# Power_cape.net
KiCad netlist of a schematic drawn in EAGLE
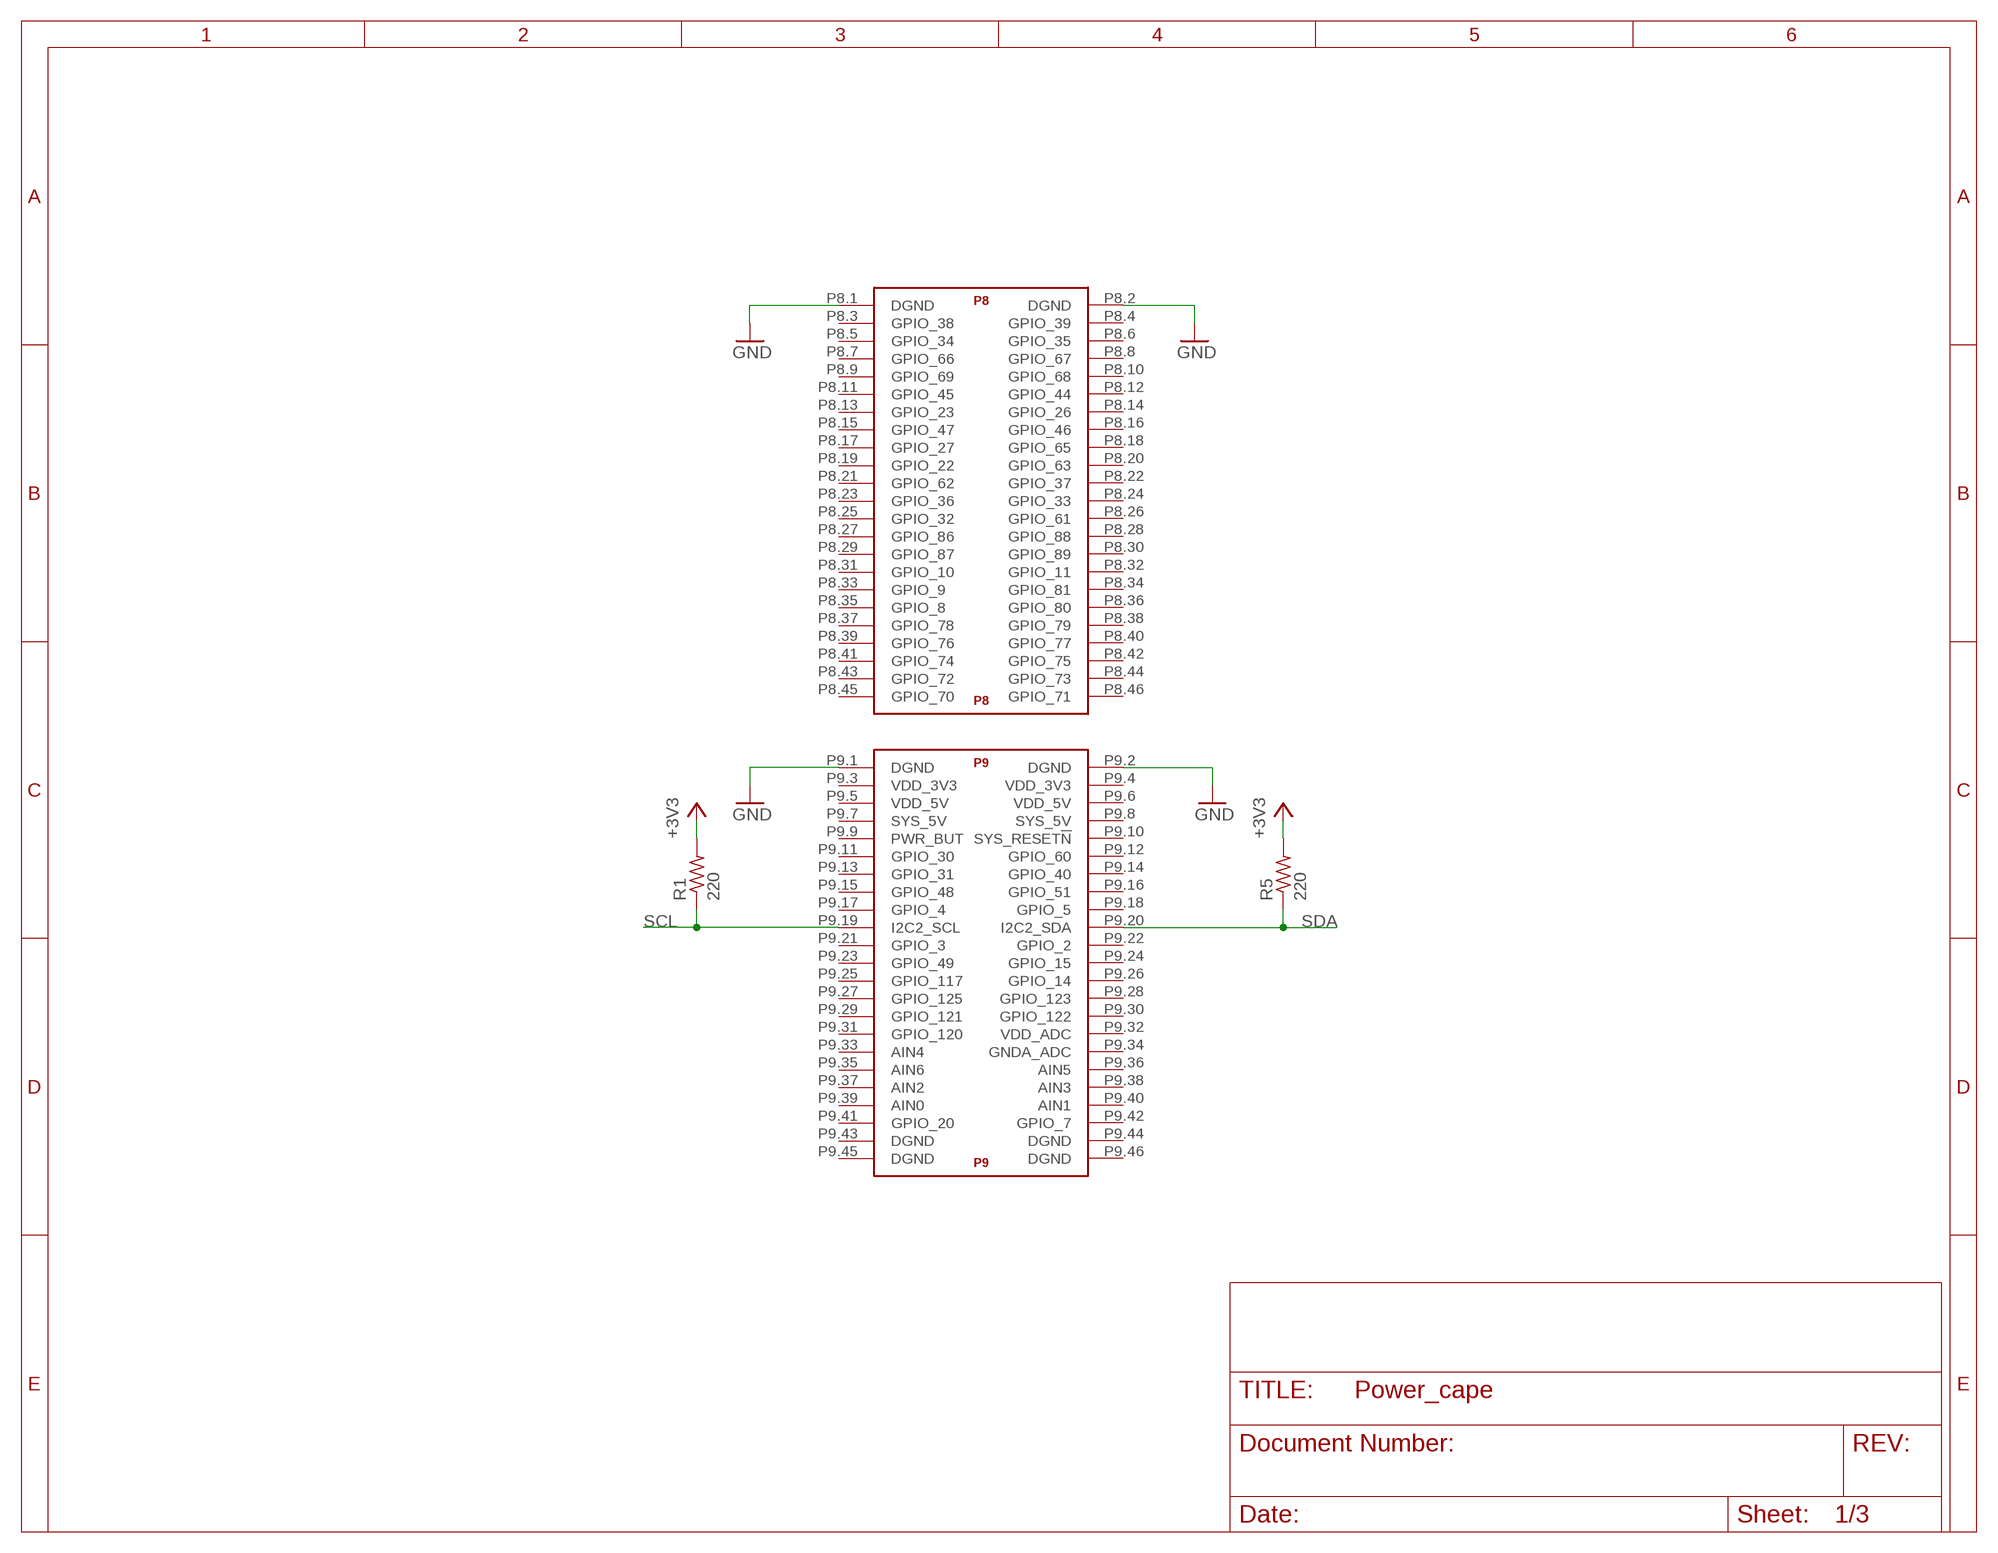
[diagram p0: schematic, sheet 1]
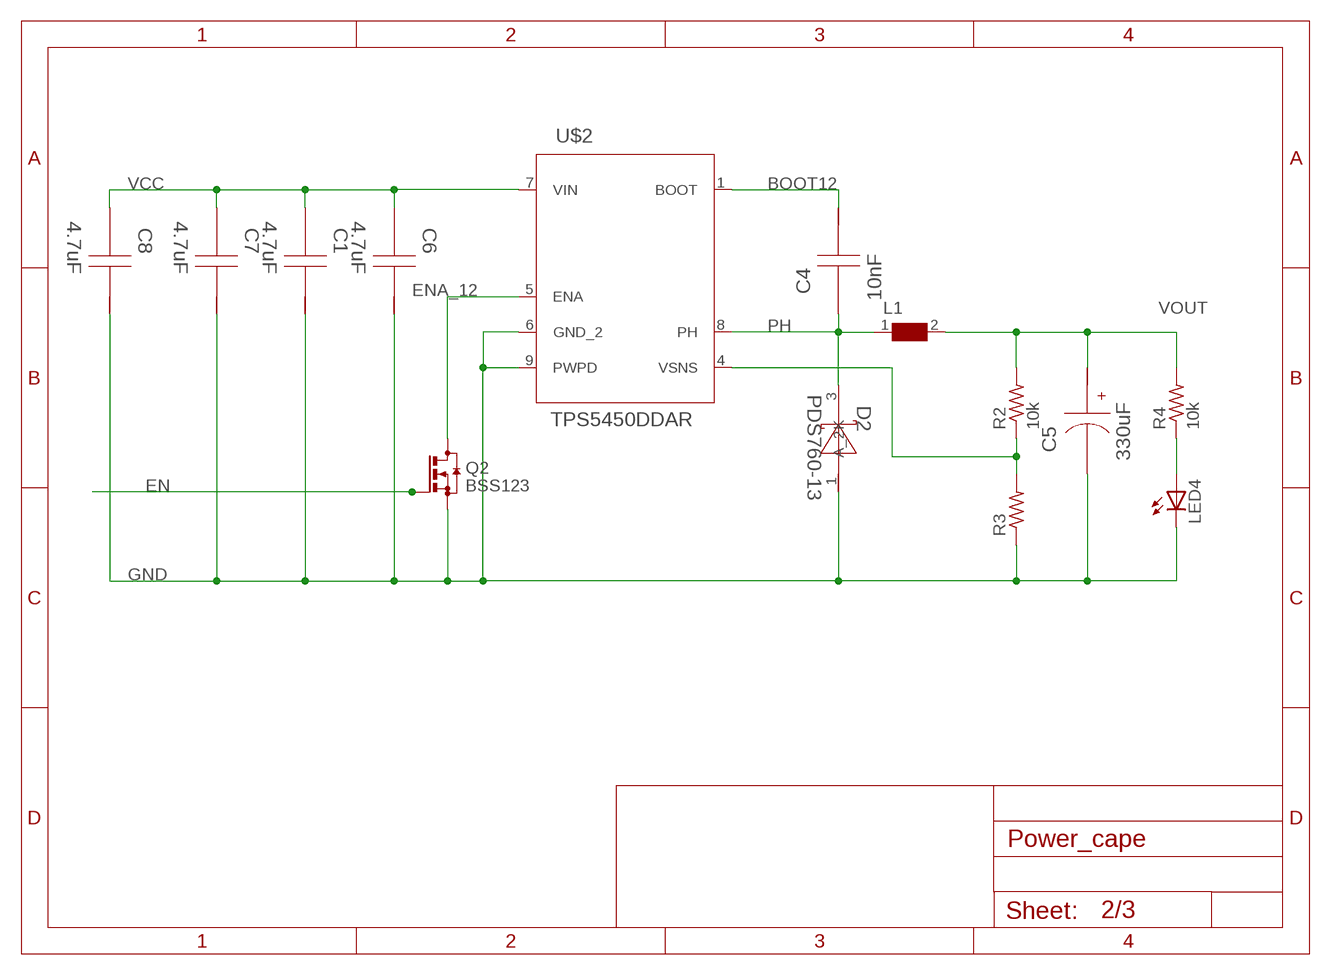
[diagram p1: schematic, sheet 2]

(export (version "E")
  (design (tool "Eeschema 10.0.6"))
  (components
    (comp (ref "C1")
      (value "4.7uF")
      (footprint "eagle-import:1206")
      (fields (field (name "MANUFACTURER_PART_NUMBER") "GRM31CR71H475KA12L"))
      (libsource (lib "eagle-import") (part "GRM31CR71H475KA12L"))
    )
    (comp (ref "C4")
      (value "10nF")
      (footprint "eagle-import:0805")
      (fields (field (name "MANUFACTURER_PART_NUMBER") "C0805C103K5RACTU"))
      (libsource (lib "eagle-import") (part "C0805C103K5RACTU"))
    )
    (comp (ref "C5")
      (value "330uF")
      (footprint "eagle-import:SM_RADIAL_10AMM")
      (fields (field (name "MANUFACTURER_PART_NUMBER") "10SVP330MX"))
      (libsource (lib "eagle-import") (part "10SVP330MX"))
    )
    (comp (ref "C6")
      (value "4.7uF")
      (footprint "eagle-import:1206")
      (fields (field (name "MANUFACTURER_PART_NUMBER") "GRM31CR71H475KA12L"))
      (libsource (lib "eagle-import") (part "GRM31CR71H475KA12L"))
    )
    (comp (ref "C7")
      (value "4.7uF")
      (footprint "eagle-import:1206")
      (fields (field (name "MANUFACTURER_PART_NUMBER") "GRM31CR71H475KA12L"))
      (libsource (lib "eagle-import") (part "GRM31CR71H475KA12L"))
    )
    (comp (ref "C8")
      (value "4.7uF")
      (footprint "eagle-import:1206")
      (fields (field (name "MANUFACTURER_PART_NUMBER") "GRM31CR71H475KA12L"))
      (libsource (lib "eagle-import") (part "GRM31CR71H475KA12L"))
    )
    (comp (ref "D2")
      (value "PDS760-13")
      (footprint "eagle-import:POWERDI5")
      (libsource (lib "eagle-import") (part "PDS760-13"))
    )
    (comp (ref "L1")
      (value "WE-HCC-7443331000_1090")
      (footprint "eagle-import:WE-HCC_1090")
      (fields (field (name "MPN") "7443331000"))
      (libsource (lib "eagle-import") (part "WE-HCC_1090-7443331000"))
    )
    (comp (ref "LED4")
      (value "LEDSML1206")
      (footprint "eagle-import:SML1206")
      (libsource (lib "eagle-import") (part "LEDSML1206"))
    )
    (comp (ref "Q2")
      (value "BSS123")
      (footprint "eagle-import:SOT23")
      (libsource (lib "eagle-import") (part "BSS123"))
    )
    (comp (ref "R2")
      (value "10k")
      (footprint "eagle-import:R1206")
      (libsource (lib "eagle-import") (part "R-US_R1206"))
    )
    (comp (ref "R3")
      (value "R-US_R1206")
      (footprint "eagle-import:R1206")
      (libsource (lib "eagle-import") (part "R-US_R1206"))
    )
    (comp (ref "R4")
      (value "10k")
      (footprint "eagle-import:R1206")
      (libsource (lib "eagle-import") (part "R-US_R1206"))
    )
    (comp (ref "U$2")
      (value "TPS5450DDAR")
      (footprint "eagle-import:R-PDSO-G8")
      (fields (field (name "MANUFACTURER_PART_NUMBER") "TPS5450DDA"))
      (libsource (lib "eagle-import") (part "TPS5450DDAR"))
    )
    (comp (ref "R1")
      (value "220")
      (footprint "eagle-import:R0805W")
      (libsource (lib "eagle-import") (part "R-US_R0805W"))
    )
    (comp (ref "R5")
      (value "220")
      (footprint "eagle-import:R0805W")
      (libsource (lib "eagle-import") (part "R-US_R0805W"))
    )
    (comp (ref "U$1")
      (value "BEAGLE_BONE_BLACK_CAPE")
      (footprint "eagle-import:BEAGLE_BONE_BLACK_CAPE")
      (libsource (lib "eagle-import") (part "BEAGLE_BONE_BLACK_CAPE"))
    )
  )
  (nets
    (net (code "1") (name "+3V3") (class "Default")
      (node (ref "R1") (pin "2") (pinfunction "2_2") (pintype "passive"))
      (node (ref "R5") (pin "2") (pinfunction "2_2") (pintype "passive"))
    )
    (net (code "2") (name "BOOT12") (class "Default")
      (node (ref "C4") (pin "1") (pinfunction "1_1") (pintype "passive"))
      (node (ref "U$2") (pin "1") (pinfunction "BOOT_1") (pintype "passive"))
    )
    (net (code "3") (name "EN") (class "Default")
      (node (ref "Q2") (pin "1") (pinfunction "G_1") (pintype "passive"))
    )
    (net (code "4") (name "ENA_12") (class "Default")
      (node (ref "Q2") (pin "3") (pinfunction "D_3") (pintype "passive"))
      (node (ref "U$2") (pin "5") (pinfunction "ENA_5") (pintype "passive"))
    )
    (net (code "5") (name "GND") (class "Default")
      (node (ref "C1") (pin "1") (pinfunction "1_1") (pintype "passive"))
      (node (ref "C5") (pin "2") (pinfunction "-_2") (pintype "passive"))
      (node (ref "C6") (pin "1") (pinfunction "1_1") (pintype "passive"))
      (node (ref "C7") (pin "1") (pinfunction "1_1") (pintype "passive"))
      (node (ref "C8") (pin "1") (pinfunction "1_1") (pintype "passive"))
      (node (ref "D2") (pin "1") (pinfunction "A_2_1") (pintype "passive"))
      (node (ref "LED4") (pin "C") (pinfunction "C_C") (pintype "passive"))
      (node (ref "Q2") (pin "2") (pinfunction "S_2") (pintype "passive"))
      (node (ref "R3") (pin "1") (pinfunction "1_1") (pintype "passive"))
      (node (ref "U$1") (pin "P8.1") (pinfunction "DGND_P8.1") (pintype "bidirectional"))
      (node (ref "U$1") (pin "P8.2") (pinfunction "DGND_P8.2") (pintype "bidirectional"))
      (node (ref "U$1") (pin "P9.1") (pinfunction "DGND_P9.1") (pintype "bidirectional"))
      (node (ref "U$1") (pin "P9.2") (pinfunction "DGND_P9.2") (pintype "bidirectional"))
      (node (ref "U$2") (pin "6") (pinfunction "GND_2_6") (pintype "passive"))
      (node (ref "U$2") (pin "9") (pinfunction "PWPD_9") (pintype "passive"))
    )
    (net (code "6") (name "Net-(LED4-PadA)") (class "Default")
      (node (ref "LED4") (pin "A") (pinfunction "A_A") (pintype "passive"))
      (node (ref "R4") (pin "1") (pinfunction "1_1") (pintype "passive"))
    )
    (net (code "7") (name "Net-(U$2-VSNS)") (class "Default")
      (node (ref "R2") (pin "1") (pinfunction "1_1") (pintype "passive"))
      (node (ref "R3") (pin "2") (pinfunction "2_2") (pintype "passive"))
      (node (ref "U$2") (pin "4") (pinfunction "VSNS_4") (pintype "passive"))
    )
    (net (code "8") (name "PH") (class "Default")
      (node (ref "C4") (pin "2") (pinfunction "2_2") (pintype "passive"))
      (node (ref "D2") (pin "3") (pinfunction "K_3") (pintype "passive"))
      (node (ref "L1") (pin "1") (pinfunction "1_1") (pintype "passive"))
      (node (ref "U$2") (pin "8") (pinfunction "PH_8") (pintype "passive"))
    )
    (net (code "9") (name "SCL") (class "Default")
      (node (ref "R1") (pin "1") (pinfunction "1_1") (pintype "passive"))
      (node (ref "U$1") (pin "P9.19") (pinfunction "I2C2_SCL_P9.19") (pintype "bidirectional"))
    )
    (net (code "10") (name "SDA") (class "Default")
      (node (ref "R5") (pin "1") (pinfunction "1_1") (pintype "passive"))
      (node (ref "U$1") (pin "P9.20") (pinfunction "I2C2_SDA_P9.20") (pintype "bidirectional"))
    )
    (net (code "11") (name "VCC") (class "Default")
      (node (ref "C1") (pin "2") (pinfunction "2_2") (pintype "passive"))
      (node (ref "C6") (pin "2") (pinfunction "2_2") (pintype "passive"))
      (node (ref "C7") (pin "2") (pinfunction "2_2") (pintype "passive"))
      (node (ref "C8") (pin "2") (pinfunction "2_2") (pintype "passive"))
      (node (ref "U$2") (pin "7") (pinfunction "VIN_7") (pintype "passive"))
    )
    (net (code "12") (name "VOUT") (class "Default")
      (node (ref "C5") (pin "1") (pinfunction "+_1") (pintype "passive"))
      (node (ref "L1") (pin "2") (pinfunction "2_2") (pintype "passive"))
      (node (ref "R2") (pin "2") (pinfunction "2_2") (pintype "passive"))
      (node (ref "R4") (pin "2") (pinfunction "2_2") (pintype "passive"))
    )
    (net (code "13") (name "unconnected-(U$1A-GPIO_8-PadP8.35)") (class "Default")
      (node (ref "U$1") (pin "P8.35") (pinfunction "GPIO_8_P8.35") (pintype "bidirectional"))
    )
    (net (code "14") (name "unconnected-(U$1A-GPIO_9-PadP8.33)") (class "Default")
      (node (ref "U$1") (pin "P8.33") (pinfunction "GPIO_9_P8.33") (pintype "bidirectional"))
    )
    (net (code "15") (name "unconnected-(U$1A-GPIO_10-PadP8.31)") (class "Default")
      (node (ref "U$1") (pin "P8.31") (pinfunction "GPIO_10_P8.31") (pintype "bidirectional"))
    )
    (net (code "16") (name "unconnected-(U$1A-GPIO_11-PadP8.32)") (class "Default")
      (node (ref "U$1") (pin "P8.32") (pinfunction "GPIO_11_P8.32") (pintype "bidirectional"))
    )
    (net (code "17") (name "unconnected-(U$1A-GPIO_22-PadP8.19)") (class "Default")
      (node (ref "U$1") (pin "P8.19") (pinfunction "GPIO_22_P8.19") (pintype "bidirectional"))
    )
    (net (code "18") (name "unconnected-(U$1A-GPIO_23-PadP8.13)") (class "Default")
      (node (ref "U$1") (pin "P8.13") (pinfunction "GPIO_23_P8.13") (pintype "bidirectional"))
    )
    (net (code "19") (name "unconnected-(U$1A-GPIO_26-PadP8.14)") (class "Default")
      (node (ref "U$1") (pin "P8.14") (pinfunction "GPIO_26_P8.14") (pintype "bidirectional"))
    )
    (net (code "20") (name "unconnected-(U$1A-GPIO_27-PadP8.17)") (class "Default")
      (node (ref "U$1") (pin "P8.17") (pinfunction "GPIO_27_P8.17") (pintype "bidirectional"))
    )
    (net (code "21") (name "unconnected-(U$1A-GPIO_32-PadP8.25)") (class "Default")
      (node (ref "U$1") (pin "P8.25") (pinfunction "GPIO_32_P8.25") (pintype "bidirectional"))
    )
    (net (code "22") (name "unconnected-(U$1A-GPIO_33-PadP8.24)") (class "Default")
      (node (ref "U$1") (pin "P8.24") (pinfunction "GPIO_33_P8.24") (pintype "bidirectional"))
    )
    (net (code "23") (name "unconnected-(U$1A-GPIO_34-PadP8.5)") (class "Default")
      (node (ref "U$1") (pin "P8.5") (pinfunction "GPIO_34_P8.5") (pintype "bidirectional"))
    )
    (net (code "24") (name "unconnected-(U$1A-GPIO_35-PadP8.6)") (class "Default")
      (node (ref "U$1") (pin "P8.6") (pinfunction "GPIO_35_P8.6") (pintype "bidirectional"))
    )
    (net (code "25") (name "unconnected-(U$1A-GPIO_36-PadP8.23)") (class "Default")
      (node (ref "U$1") (pin "P8.23") (pinfunction "GPIO_36_P8.23") (pintype "bidirectional"))
    )
    (net (code "26") (name "unconnected-(U$1A-GPIO_37-PadP8.22)") (class "Default")
      (node (ref "U$1") (pin "P8.22") (pinfunction "GPIO_37_P8.22") (pintype "bidirectional"))
    )
    (net (code "27") (name "unconnected-(U$1A-GPIO_38-PadP8.3)") (class "Default")
      (node (ref "U$1") (pin "P8.3") (pinfunction "GPIO_38_P8.3") (pintype "bidirectional"))
    )
    (net (code "28") (name "unconnected-(U$1A-GPIO_39-PadP8.4)") (class "Default")
      (node (ref "U$1") (pin "P8.4") (pinfunction "GPIO_39_P8.4") (pintype "bidirectional"))
    )
    (net (code "29") (name "unconnected-(U$1A-GPIO_44-PadP8.12)") (class "Default")
      (node (ref "U$1") (pin "P8.12") (pinfunction "GPIO_44_P8.12") (pintype "bidirectional"))
    )
    (net (code "30") (name "unconnected-(U$1A-GPIO_45-PadP8.11)") (class "Default")
      (node (ref "U$1") (pin "P8.11") (pinfunction "GPIO_45_P8.11") (pintype "bidirectional"))
    )
    (net (code "31") (name "unconnected-(U$1A-GPIO_46-PadP8.16)") (class "Default")
      (node (ref "U$1") (pin "P8.16") (pinfunction "GPIO_46_P8.16") (pintype "bidirectional"))
    )
    (net (code "32") (name "unconnected-(U$1A-GPIO_47-PadP8.15)") (class "Default")
      (node (ref "U$1") (pin "P8.15") (pinfunction "GPIO_47_P8.15") (pintype "bidirectional"))
    )
    (net (code "33") (name "unconnected-(U$1A-GPIO_61-PadP8.26)") (class "Default")
      (node (ref "U$1") (pin "P8.26") (pinfunction "GPIO_61_P8.26") (pintype "bidirectional"))
    )
    (net (code "34") (name "unconnected-(U$1A-GPIO_62-PadP8.21)") (class "Default")
      (node (ref "U$1") (pin "P8.21") (pinfunction "GPIO_62_P8.21") (pintype "bidirectional"))
    )
    (net (code "35") (name "unconnected-(U$1A-GPIO_63-PadP8.20)") (class "Default")
      (node (ref "U$1") (pin "P8.20") (pinfunction "GPIO_63_P8.20") (pintype "bidirectional"))
    )
    (net (code "36") (name "unconnected-(U$1A-GPIO_65-PadP8.18)") (class "Default")
      (node (ref "U$1") (pin "P8.18") (pinfunction "GPIO_65_P8.18") (pintype "bidirectional"))
    )
    (net (code "37") (name "unconnected-(U$1A-GPIO_66-PadP8.7)") (class "Default")
      (node (ref "U$1") (pin "P8.7") (pinfunction "GPIO_66_P8.7") (pintype "bidirectional"))
    )
    (net (code "38") (name "unconnected-(U$1A-GPIO_67-PadP8.8)") (class "Default")
      (node (ref "U$1") (pin "P8.8") (pinfunction "GPIO_67_P8.8") (pintype "bidirectional"))
    )
    (net (code "39") (name "unconnected-(U$1A-GPIO_68-PadP8.10)") (class "Default")
      (node (ref "U$1") (pin "P8.10") (pinfunction "GPIO_68_P8.10") (pintype "bidirectional"))
    )
    (net (code "40") (name "unconnected-(U$1A-GPIO_69-PadP8.9)") (class "Default")
      (node (ref "U$1") (pin "P8.9") (pinfunction "GPIO_69_P8.9") (pintype "bidirectional"))
    )
    (net (code "41") (name "unconnected-(U$1A-GPIO_70-PadP8.45)") (class "Default")
      (node (ref "U$1") (pin "P8.45") (pinfunction "GPIO_70_P8.45") (pintype "bidirectional"))
    )
    (net (code "42") (name "unconnected-(U$1A-GPIO_71-PadP8.46)") (class "Default")
      (node (ref "U$1") (pin "P8.46") (pinfunction "GPIO_71_P8.46") (pintype "bidirectional"))
    )
    (net (code "43") (name "unconnected-(U$1A-GPIO_72-PadP8.43)") (class "Default")
      (node (ref "U$1") (pin "P8.43") (pinfunction "GPIO_72_P8.43") (pintype "bidirectional"))
    )
    (net (code "44") (name "unconnected-(U$1A-GPIO_73-PadP8.44)") (class "Default")
      (node (ref "U$1") (pin "P8.44") (pinfunction "GPIO_73_P8.44") (pintype "bidirectional"))
    )
    (net (code "45") (name "unconnected-(U$1A-GPIO_74-PadP8.41)") (class "Default")
      (node (ref "U$1") (pin "P8.41") (pinfunction "GPIO_74_P8.41") (pintype "bidirectional"))
    )
    (net (code "46") (name "unconnected-(U$1A-GPIO_75-PadP8.42)") (class "Default")
      (node (ref "U$1") (pin "P8.42") (pinfunction "GPIO_75_P8.42") (pintype "bidirectional"))
    )
    (net (code "47") (name "unconnected-(U$1A-GPIO_76-PadP8.39)") (class "Default")
      (node (ref "U$1") (pin "P8.39") (pinfunction "GPIO_76_P8.39") (pintype "bidirectional"))
    )
    (net (code "48") (name "unconnected-(U$1A-GPIO_77-PadP8.40)") (class "Default")
      (node (ref "U$1") (pin "P8.40") (pinfunction "GPIO_77_P8.40") (pintype "bidirectional"))
    )
    (net (code "49") (name "unconnected-(U$1A-GPIO_78-PadP8.37)") (class "Default")
      (node (ref "U$1") (pin "P8.37") (pinfunction "GPIO_78_P8.37") (pintype "bidirectional"))
    )
    (net (code "50") (name "unconnected-(U$1A-GPIO_79-PadP8.38)") (class "Default")
      (node (ref "U$1") (pin "P8.38") (pinfunction "GPIO_79_P8.38") (pintype "bidirectional"))
    )
    (net (code "51") (name "unconnected-(U$1A-GPIO_80-PadP8.36)") (class "Default")
      (node (ref "U$1") (pin "P8.36") (pinfunction "GPIO_80_P8.36") (pintype "bidirectional"))
    )
    (net (code "52") (name "unconnected-(U$1A-GPIO_81-PadP8.34)") (class "Default")
      (node (ref "U$1") (pin "P8.34") (pinfunction "GPIO_81_P8.34") (pintype "bidirectional"))
    )
    (net (code "53") (name "unconnected-(U$1A-GPIO_86-PadP8.27)") (class "Default")
      (node (ref "U$1") (pin "P8.27") (pinfunction "GPIO_86_P8.27") (pintype "bidirectional"))
    )
    (net (code "54") (name "unconnected-(U$1A-GPIO_87-PadP8.29)") (class "Default")
      (node (ref "U$1") (pin "P8.29") (pinfunction "GPIO_87_P8.29") (pintype "bidirectional"))
    )
    (net (code "55") (name "unconnected-(U$1A-GPIO_88-PadP8.28)") (class "Default")
      (node (ref "U$1") (pin "P8.28") (pinfunction "GPIO_88_P8.28") (pintype "bidirectional"))
    )
    (net (code "56") (name "unconnected-(U$1A-GPIO_89-PadP8.30)") (class "Default")
      (node (ref "U$1") (pin "P8.30") (pinfunction "GPIO_89_P8.30") (pintype "bidirectional"))
    )
    (net (code "57") (name "unconnected-(U$1B-AIN0-PadP9.39)") (class "Default")
      (node (ref "U$1") (pin "P9.39") (pinfunction "AIN0_P9.39") (pintype "bidirectional"))
    )
    (net (code "58") (name "unconnected-(U$1B-AIN1-PadP9.40)") (class "Default")
      (node (ref "U$1") (pin "P9.40") (pinfunction "AIN1_P9.40") (pintype "bidirectional"))
    )
    (net (code "59") (name "unconnected-(U$1B-AIN2-PadP9.37)") (class "Default")
      (node (ref "U$1") (pin "P9.37") (pinfunction "AIN2_P9.37") (pintype "bidirectional"))
    )
    (net (code "60") (name "unconnected-(U$1B-AIN3-PadP9.38)") (class "Default")
      (node (ref "U$1") (pin "P9.38") (pinfunction "AIN3_P9.38") (pintype "bidirectional"))
    )
    (net (code "61") (name "unconnected-(U$1B-AIN4-PadP9.33)") (class "Default")
      (node (ref "U$1") (pin "P9.33") (pinfunction "AIN4_P9.33") (pintype "bidirectional"))
    )
    (net (code "62") (name "unconnected-(U$1B-AIN5-PadP9.36)") (class "Default")
      (node (ref "U$1") (pin "P9.36") (pinfunction "AIN5_P9.36") (pintype "bidirectional"))
    )
    (net (code "63") (name "unconnected-(U$1B-AIN6-PadP9.35)") (class "Default")
      (node (ref "U$1") (pin "P9.35") (pinfunction "AIN6_P9.35") (pintype "bidirectional"))
    )
    (net (code "64") (name "unconnected-(U$1B-DGND-PadP9.43)") (class "Default")
      (node (ref "U$1") (pin "P9.43") (pinfunction "DGND_P9.43") (pintype "bidirectional"))
    )
    (net (code "65") (name "unconnected-(U$1B-DGND-PadP9.44)") (class "Default")
      (node (ref "U$1") (pin "P9.44") (pinfunction "DGND_P9.44") (pintype "bidirectional"))
    )
    (net (code "66") (name "unconnected-(U$1B-DGND-PadP9.45)") (class "Default")
      (node (ref "U$1") (pin "P9.45") (pinfunction "DGND_P9.45") (pintype "bidirectional"))
    )
    (net (code "67") (name "unconnected-(U$1B-DGND-PadP9.46)") (class "Default")
      (node (ref "U$1") (pin "P9.46") (pinfunction "DGND_P9.46") (pintype "bidirectional"))
    )
    (net (code "68") (name "unconnected-(U$1B-GNDA_ADC-PadP9.34)") (class "Default")
      (node (ref "U$1") (pin "P9.34") (pinfunction "GNDA_ADC_P9.34") (pintype "bidirectional"))
    )
    (net (code "69") (name "unconnected-(U$1B-GPIO_2-PadP9.22)") (class "Default")
      (node (ref "U$1") (pin "P9.22") (pinfunction "GPIO_2_P9.22") (pintype "bidirectional"))
    )
    (net (code "70") (name "unconnected-(U$1B-GPIO_3-PadP9.21)") (class "Default")
      (node (ref "U$1") (pin "P9.21") (pinfunction "GPIO_3_P9.21") (pintype "bidirectional"))
    )
    (net (code "71") (name "unconnected-(U$1B-GPIO_4-PadP9.17)") (class "Default")
      (node (ref "U$1") (pin "P9.17") (pinfunction "GPIO_4_P9.17") (pintype "bidirectional"))
    )
    (net (code "72") (name "unconnected-(U$1B-GPIO_5-PadP9.18)") (class "Default")
      (node (ref "U$1") (pin "P9.18") (pinfunction "GPIO_5_P9.18") (pintype "bidirectional"))
    )
    (net (code "73") (name "unconnected-(U$1B-GPIO_7-PadP9.42)") (class "Default")
      (node (ref "U$1") (pin "P9.42") (pinfunction "GPIO_7_P9.42") (pintype "bidirectional"))
    )
    (net (code "74") (name "unconnected-(U$1B-GPIO_14-PadP9.26)") (class "Default")
      (node (ref "U$1") (pin "P9.26") (pinfunction "GPIO_14_P9.26") (pintype "bidirectional"))
    )
    (net (code "75") (name "unconnected-(U$1B-GPIO_15-PadP9.24)") (class "Default")
      (node (ref "U$1") (pin "P9.24") (pinfunction "GPIO_15_P9.24") (pintype "bidirectional"))
    )
    (net (code "76") (name "unconnected-(U$1B-GPIO_20-PadP9.41)") (class "Default")
      (node (ref "U$1") (pin "P9.41") (pinfunction "GPIO_20_P9.41") (pintype "bidirectional"))
    )
    (net (code "77") (name "unconnected-(U$1B-GPIO_30-PadP9.11)") (class "Default")
      (node (ref "U$1") (pin "P9.11") (pinfunction "GPIO_30_P9.11") (pintype "bidirectional"))
    )
    (net (code "78") (name "unconnected-(U$1B-GPIO_31-PadP9.13)") (class "Default")
      (node (ref "U$1") (pin "P9.13") (pinfunction "GPIO_31_P9.13") (pintype "bidirectional"))
    )
    (net (code "79") (name "unconnected-(U$1B-GPIO_40-PadP9.14)") (class "Default")
      (node (ref "U$1") (pin "P9.14") (pinfunction "GPIO_40_P9.14") (pintype "bidirectional"))
    )
    (net (code "80") (name "unconnected-(U$1B-GPIO_48-PadP9.15)") (class "Default")
      (node (ref "U$1") (pin "P9.15") (pinfunction "GPIO_48_P9.15") (pintype "bidirectional"))
    )
    (net (code "81") (name "unconnected-(U$1B-GPIO_49-PadP9.23)") (class "Default")
      (node (ref "U$1") (pin "P9.23") (pinfunction "GPIO_49_P9.23") (pintype "bidirectional"))
    )
    (net (code "82") (name "unconnected-(U$1B-GPIO_51-PadP9.16)") (class "Default")
      (node (ref "U$1") (pin "P9.16") (pinfunction "GPIO_51_P9.16") (pintype "bidirectional"))
    )
    (net (code "83") (name "unconnected-(U$1B-GPIO_60-PadP9.12)") (class "Default")
      (node (ref "U$1") (pin "P9.12") (pinfunction "GPIO_60_P9.12") (pintype "bidirectional"))
    )
    (net (code "84") (name "unconnected-(U$1B-GPIO_117-PadP9.25)") (class "Default")
      (node (ref "U$1") (pin "P9.25") (pinfunction "GPIO_117_P9.25") (pintype "bidirectional"))
    )
    (net (code "85") (name "unconnected-(U$1B-GPIO_120-PadP9.31)") (class "Default")
      (node (ref "U$1") (pin "P9.31") (pinfunction "GPIO_120_P9.31") (pintype "bidirectional"))
    )
    (net (code "86") (name "unconnected-(U$1B-GPIO_121-PadP9.29)") (class "Default")
      (node (ref "U$1") (pin "P9.29") (pinfunction "GPIO_121_P9.29") (pintype "bidirectional"))
    )
    (net (code "87") (name "unconnected-(U$1B-GPIO_122-PadP9.30)") (class "Default")
      (node (ref "U$1") (pin "P9.30") (pinfunction "GPIO_122_P9.30") (pintype "bidirectional"))
    )
    (net (code "88") (name "unconnected-(U$1B-GPIO_123-PadP9.28)") (class "Default")
      (node (ref "U$1") (pin "P9.28") (pinfunction "GPIO_123_P9.28") (pintype "bidirectional"))
    )
    (net (code "89") (name "unconnected-(U$1B-GPIO_125-PadP9.27)") (class "Default")
      (node (ref "U$1") (pin "P9.27") (pinfunction "GPIO_125_P9.27") (pintype "bidirectional"))
    )
    (net (code "90") (name "unconnected-(U$1B-PWR_BUT-PadP9.9)") (class "Default")
      (node (ref "U$1") (pin "P9.9") (pinfunction "PWR_BUT_P9.9") (pintype "bidirectional"))
    )
    (net (code "91") (name "unconnected-(U$1B-SYS_5V-PadP9.7)") (class "Default")
      (node (ref "U$1") (pin "P9.7") (pinfunction "SYS_5V_P9.7") (pintype "bidirectional"))
    )
    (net (code "92") (name "unconnected-(U$1B-SYS_5V-PadP9.8)") (class "Default")
      (node (ref "U$1") (pin "P9.8") (pinfunction "SYS_5V_P9.8") (pintype "bidirectional"))
    )
    (net (code "93") (name "unconnected-(U$1B-SYS_RESET~{N}-PadP9.10)") (class "Default")
      (node (ref "U$1") (pin "P9.10") (pinfunction "SYS_RESET~{N}_P9.10") (pintype "bidirectional"))
    )
    (net (code "94") (name "unconnected-(U$1B-VDD_3V3-PadP9.3)") (class "Default")
      (node (ref "U$1") (pin "P9.3") (pinfunction "VDD_3V3_P9.3") (pintype "bidirectional"))
    )
    (net (code "95") (name "unconnected-(U$1B-VDD_3V3-PadP9.4)") (class "Default")
      (node (ref "U$1") (pin "P9.4") (pinfunction "VDD_3V3_P9.4") (pintype "bidirectional"))
    )
    (net (code "96") (name "unconnected-(U$1B-VDD_5V-PadP9.5)") (class "Default")
      (node (ref "U$1") (pin "P9.5") (pinfunction "VDD_5V_P9.5") (pintype "bidirectional"))
    )
    (net (code "97") (name "unconnected-(U$1B-VDD_5V-PadP9.6)") (class "Default")
      (node (ref "U$1") (pin "P9.6") (pinfunction "VDD_5V_P9.6") (pintype "bidirectional"))
    )
    (net (code "98") (name "unconnected-(U$1B-VDD_ADC-PadP9.32)") (class "Default")
      (node (ref "U$1") (pin "P9.32") (pinfunction "VDD_ADC_P9.32") (pintype "bidirectional"))
    )
  )
)
